# Tapuino_1_5.net
KiCad netlist of a schematic drawn in EAGLE
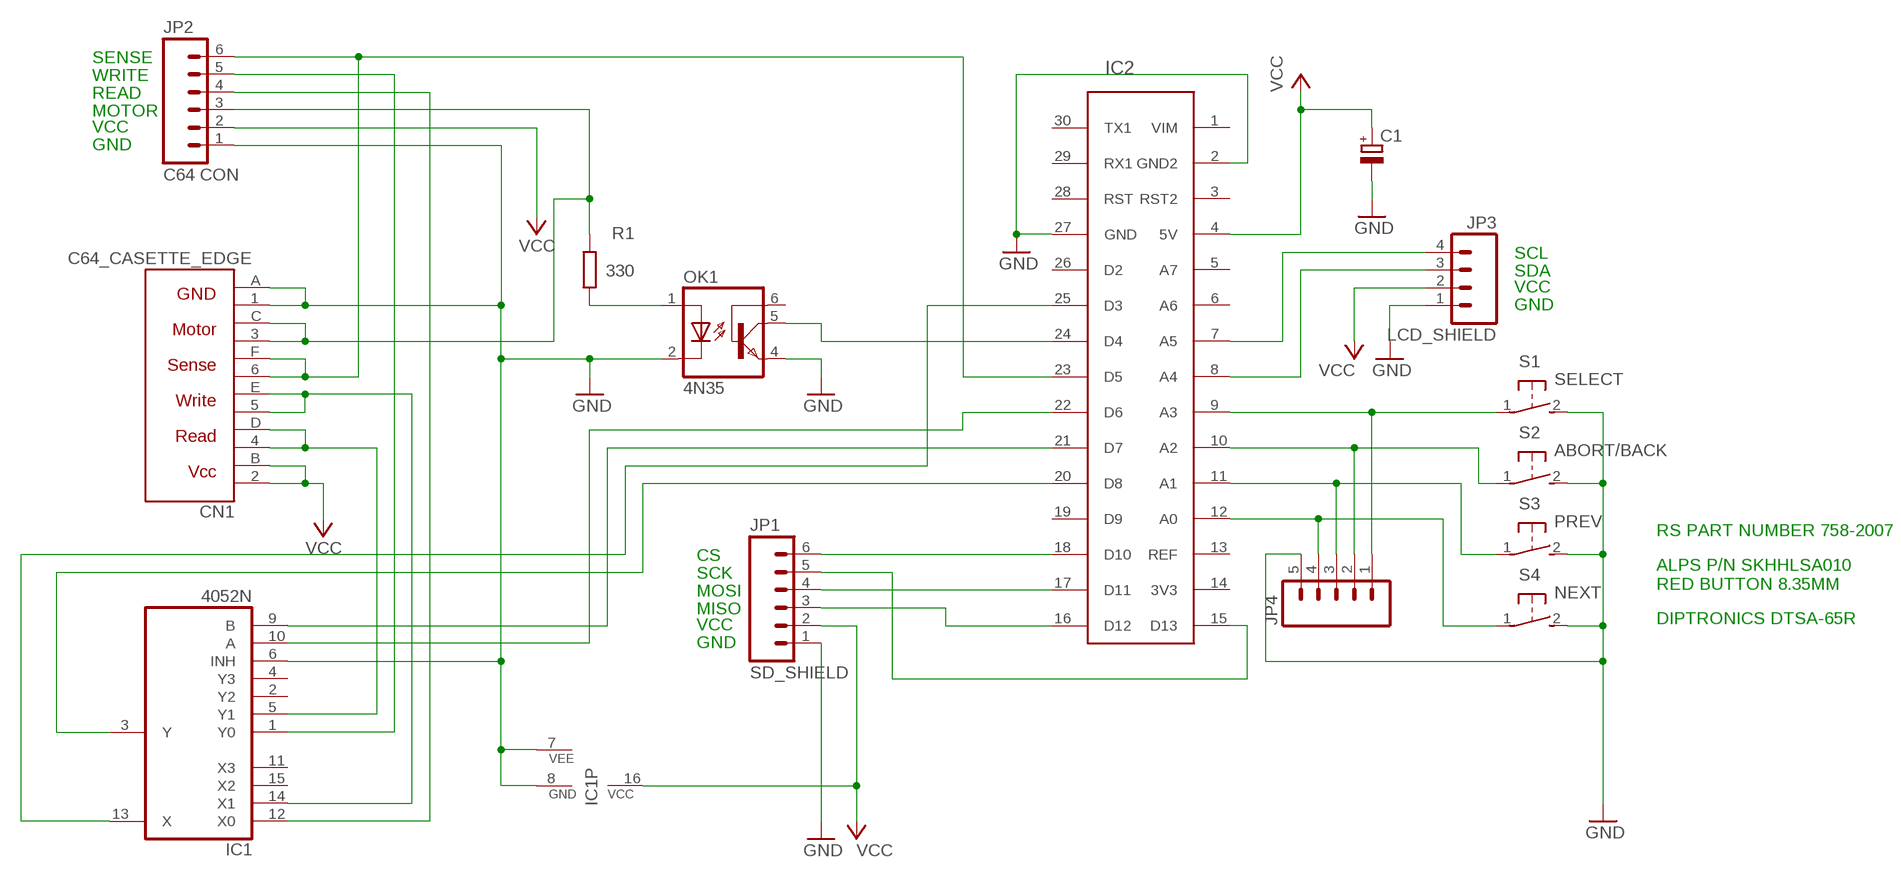
[diagram p0: schematic, sheet 1]

(export (version "E")
  (design (tool "Eeschema 10.0.6"))
  (components
    (comp (ref "C1")
      (value "CPOL-EUE2.5-6")
      (footprint "eagle-import:E2,5-6")
      (libsource (lib "eagle-import") (part "CPOL-EUE2.5-6"))
    )
    (comp (ref "CN1")
      (value "C64_CASETTE_EDGE")
      (footprint "eagle-import:C64_CASSETTE")
      (libsource (lib "eagle-import") (part "C64_CASETTE_EDGE"))
    )
    (comp (ref "IC1")
      (value "4052N")
      (footprint "eagle-import:DIL16")
      (libsource (lib "eagle-import") (part "4052N"))
    )
    (comp (ref "IC2")
      (value "ARDUINO_NANO_V3")
      (footprint "eagle-import:NANO_V3")
      (libsource (lib "eagle-import") (part "ARDUINO_NANO_V3"))
    )
    (comp (ref "JP1")
      (value "SD_SHIELD")
      (footprint "eagle-import:1X06_LOCK_LONGPADS")
      (libsource (lib "eagle-import") (part "M06LOCK_LONGPADS"))
    )
    (comp (ref "JP2")
      (value "C64 CON")
      (footprint "eagle-import:1X06_LOCK_LONGPADS")
      (libsource (lib "eagle-import") (part "M06LOCK_LONGPADS"))
    )
    (comp (ref "JP3")
      (value "LCD_SHIELD")
      (footprint "eagle-import:1X04_LOCK_LONGPADS")
      (libsource (lib "eagle-import") (part "M04LOCK_LONGPADS"))
    )
    (comp (ref "JP4")
      (value "M05LOCK_LONGPADS")
      (footprint "eagle-import:1X05_LOCK_LONGPADS")
      (libsource (lib "eagle-import") (part "M05LOCK_LONGPADS"))
    )
    (comp (ref "OK1")
      (value "4N35")
      (footprint "eagle-import:DIL06")
      (fields (field (name "MF") "FAIRCHILD SEMICONDUCTOR"))
      (libsource (lib "eagle-import") (part "4N35"))
    )
    (comp (ref "R1")
      (value "330")
      (footprint "eagle-import:0207_10")
      (libsource (lib "eagle-import") (part "R-EU_0207/10"))
    )
    (comp (ref "S1")
      (value "SELECT")
      (footprint "eagle-import:B3F-31XX")
      (fields (field (name "MPN") "B3F-3100"))
      (libsource (lib "eagle-import") (part "31-XX"))
    )
    (comp (ref "S2")
      (value "ABORT/BACK")
      (footprint "eagle-import:B3F-31XX")
      (fields (field (name "MPN") "B3F-3100"))
      (libsource (lib "eagle-import") (part "31-XX"))
    )
    (comp (ref "S3")
      (value "PREV")
      (footprint "eagle-import:B3F-31XX")
      (fields (field (name "MPN") "B3F-3100"))
      (libsource (lib "eagle-import") (part "31-XX"))
    )
    (comp (ref "S4")
      (value "NEXT")
      (footprint "eagle-import:B3F-31XX")
      (fields (field (name "MPN") "B3F-3100"))
      (libsource (lib "eagle-import") (part "31-XX"))
    )
  )
  (nets
    (net (code "1") (name "GND") (class "Default")
      (node (ref "C1") (pin "-") (pinfunction "-_-") (pintype "passive"))
      (node (ref "CN1") (pin "1") (pinfunction "GND1_1") (pintype "power_in"))
      (node (ref "CN1") (pin "A") (pinfunction "GND2_A") (pintype "power_in"))
      (node (ref "IC1") (pin "6") (pinfunction "INH_6") (pintype "input"))
      (node (ref "IC1") (pin "7") (pinfunction "VEE_7") (pintype "power_in"))
      (node (ref "IC1") (pin "8") (pinfunction "GND_8") (pintype "power_in"))
      (node (ref "IC2") (pin "2") (pinfunction "GND2_2") (pintype "bidirectional"))
      (node (ref "IC2") (pin "27") (pinfunction "GND_27") (pintype "bidirectional"))
      (node (ref "JP1") (pin "1") (pinfunction "1_1") (pintype "passive"))
      (node (ref "JP2") (pin "1") (pinfunction "1_1") (pintype "passive"))
      (node (ref "JP3") (pin "1") (pinfunction "1_1") (pintype "passive"))
      (node (ref "JP4") (pin "5") (pinfunction "5_5") (pintype "passive"))
      (node (ref "OK1") (pin "2") (pinfunction "C_2") (pintype "passive"))
      (node (ref "OK1") (pin "4") (pinfunction "EMI_4") (pintype "passive"))
      (node (ref "S1") (pin "2") (pinfunction "S_2") (pintype "passive"))
      (node (ref "S2") (pin "2") (pinfunction "S_2") (pintype "passive"))
      (node (ref "S3") (pin "2") (pinfunction "S_2") (pintype "passive"))
      (node (ref "S4") (pin "2") (pinfunction "S_2") (pintype "passive"))
    )
    (net (code "2") (name "Net-(CN1-MOTOR1)") (class "Default")
      (node (ref "CN1") (pin "3") (pinfunction "MOTOR1_3") (pintype "output"))
      (node (ref "CN1") (pin "C") (pinfunction "MOTOR2_C") (pintype "output"))
      (node (ref "JP2") (pin "3") (pinfunction "3_3") (pintype "passive"))
      (node (ref "R1") (pin "2") (pinfunction "2_2") (pintype "passive"))
    )
    (net (code "3") (name "Net-(CN1-READ1)") (class "Default")
      (node (ref "CN1") (pin "4") (pinfunction "READ1_4") (pintype "output"))
      (node (ref "CN1") (pin "D") (pinfunction "READ2_D") (pintype "output"))
      (node (ref "IC1") (pin "5") (pinfunction "Y1_5") (pintype "bidirectional"))
    )
    (net (code "4") (name "Net-(CN1-SENSE1)") (class "Default")
      (node (ref "CN1") (pin "6") (pinfunction "SENSE1_6") (pintype "input"))
      (node (ref "CN1") (pin "F") (pinfunction "SENSE2_F") (pintype "input"))
      (node (ref "IC2") (pin "23") (pinfunction "D5_23") (pintype "bidirectional"))
      (node (ref "JP2") (pin "6") (pinfunction "6_6") (pintype "passive"))
    )
    (net (code "5") (name "Net-(CN1-WRITE1)") (class "Default")
      (node (ref "CN1") (pin "5") (pinfunction "WRITE1_5") (pintype "input"))
      (node (ref "CN1") (pin "E") (pinfunction "WRITE2_E") (pintype "input"))
      (node (ref "IC1") (pin "14") (pinfunction "X1_14") (pintype "bidirectional"))
    )
    (net (code "6") (name "Net-(IC1A-A)") (class "Default")
      (node (ref "IC1") (pin "10") (pinfunction "A_10") (pintype "input"))
      (node (ref "IC2") (pin "22") (pinfunction "D6_22") (pintype "bidirectional"))
    )
    (net (code "7") (name "Net-(IC1A-B)") (class "Default")
      (node (ref "IC1") (pin "9") (pinfunction "B_9") (pintype "input"))
      (node (ref "IC2") (pin "21") (pinfunction "D7_21") (pintype "bidirectional"))
    )
    (net (code "8") (name "Net-(IC1A-X)") (class "Default")
      (node (ref "IC1") (pin "13") (pinfunction "X_13") (pintype "bidirectional"))
      (node (ref "IC2") (pin "25") (pinfunction "D3_25") (pintype "bidirectional"))
    )
    (net (code "9") (name "Net-(IC1A-X0)") (class "Default")
      (node (ref "IC1") (pin "12") (pinfunction "X0_12") (pintype "bidirectional"))
      (node (ref "JP2") (pin "4") (pinfunction "4_4") (pintype "passive"))
    )
    (net (code "10") (name "Net-(IC1A-Y)") (class "Default")
      (node (ref "IC1") (pin "3") (pinfunction "Y_3") (pintype "bidirectional"))
      (node (ref "IC2") (pin "20") (pinfunction "D8_20") (pintype "bidirectional"))
    )
    (net (code "11") (name "Net-(IC1A-Y0)") (class "Default")
      (node (ref "IC1") (pin "1") (pinfunction "Y0_1") (pintype "bidirectional"))
      (node (ref "JP2") (pin "5") (pinfunction "5_5") (pintype "passive"))
    )
    (net (code "12") (name "Net-(IC2-A0)") (class "Default")
      (node (ref "IC2") (pin "12") (pinfunction "A0_12") (pintype "bidirectional"))
      (node (ref "JP4") (pin "4") (pinfunction "4_4") (pintype "passive"))
      (node (ref "S4") (pin "1") (pinfunction "P_1") (pintype "passive"))
    )
    (net (code "13") (name "Net-(IC2-A1)") (class "Default")
      (node (ref "IC2") (pin "11") (pinfunction "A1_11") (pintype "bidirectional"))
      (node (ref "JP4") (pin "3") (pinfunction "3_3") (pintype "passive"))
      (node (ref "S3") (pin "1") (pinfunction "P_1") (pintype "passive"))
    )
    (net (code "14") (name "Net-(IC2-A2)") (class "Default")
      (node (ref "IC2") (pin "10") (pinfunction "A2_10") (pintype "bidirectional"))
      (node (ref "JP4") (pin "2") (pinfunction "2_2") (pintype "passive"))
      (node (ref "S2") (pin "1") (pinfunction "P_1") (pintype "passive"))
    )
    (net (code "15") (name "Net-(IC2-A3)") (class "Default")
      (node (ref "IC2") (pin "9") (pinfunction "A3_9") (pintype "bidirectional"))
      (node (ref "JP4") (pin "1") (pinfunction "1_1") (pintype "passive"))
      (node (ref "S1") (pin "1") (pinfunction "P_1") (pintype "passive"))
    )
    (net (code "16") (name "Net-(IC2-A4)") (class "Default")
      (node (ref "IC2") (pin "8") (pinfunction "A4_8") (pintype "bidirectional"))
      (node (ref "JP3") (pin "3") (pinfunction "3_3") (pintype "passive"))
    )
    (net (code "17") (name "Net-(IC2-A5)") (class "Default")
      (node (ref "IC2") (pin "7") (pinfunction "A5_7") (pintype "bidirectional"))
      (node (ref "JP3") (pin "4") (pinfunction "4_4") (pintype "passive"))
    )
    (net (code "18") (name "Net-(IC2-D4)") (class "Default")
      (node (ref "IC2") (pin "24") (pinfunction "D4_24") (pintype "bidirectional"))
      (node (ref "OK1") (pin "5") (pinfunction "COL_5") (pintype "passive"))
    )
    (net (code "19") (name "Net-(IC2-D10)") (class "Default")
      (node (ref "IC2") (pin "18") (pinfunction "D10_18") (pintype "bidirectional"))
      (node (ref "JP1") (pin "6") (pinfunction "6_6") (pintype "passive"))
    )
    (net (code "20") (name "Net-(IC2-D11)") (class "Default")
      (node (ref "IC2") (pin "17") (pinfunction "D11_17") (pintype "bidirectional"))
      (node (ref "JP1") (pin "4") (pinfunction "4_4") (pintype "passive"))
    )
    (net (code "21") (name "Net-(IC2-D12)") (class "Default")
      (node (ref "IC2") (pin "16") (pinfunction "D12_16") (pintype "bidirectional"))
      (node (ref "JP1") (pin "3") (pinfunction "3_3") (pintype "passive"))
    )
    (net (code "22") (name "Net-(IC2-D13)") (class "Default")
      (node (ref "IC2") (pin "15") (pinfunction "D13_15") (pintype "bidirectional"))
      (node (ref "JP1") (pin "5") (pinfunction "5_5") (pintype "passive"))
    )
    (net (code "23") (name "Net-(OK1-A)") (class "Default")
      (node (ref "OK1") (pin "1") (pinfunction "A_1") (pintype "passive"))
      (node (ref "R1") (pin "1") (pinfunction "1_1") (pintype "passive"))
    )
    (net (code "24") (name "VCC") (class "Default")
      (node (ref "C1") (pin "+") (pinfunction "+_+") (pintype "passive"))
      (node (ref "CN1") (pin "2") (pinfunction "VCC1_2") (pintype "power_in"))
      (node (ref "CN1") (pin "B") (pinfunction "VCC2_B") (pintype "power_in"))
      (node (ref "IC1") (pin "16") (pinfunction "VCC_16") (pintype "power_in"))
      (node (ref "IC2") (pin "4") (pinfunction "5V_4") (pintype "bidirectional"))
      (node (ref "JP1") (pin "2") (pinfunction "2_2") (pintype "passive"))
      (node (ref "JP2") (pin "2") (pinfunction "2_2") (pintype "passive"))
      (node (ref "JP3") (pin "2") (pinfunction "2_2") (pintype "passive"))
    )
    (net (code "25") (name "unconnected-(IC1A-X2-Pad15)") (class "Default")
      (node (ref "IC1") (pin "15") (pinfunction "X2_15") (pintype "bidirectional"))
    )
    (net (code "26") (name "unconnected-(IC1A-X3-Pad11)") (class "Default")
      (node (ref "IC1") (pin "11") (pinfunction "X3_11") (pintype "bidirectional"))
    )
    (net (code "27") (name "unconnected-(IC1A-Y2-Pad2)") (class "Default")
      (node (ref "IC1") (pin "2") (pinfunction "Y2_2") (pintype "bidirectional"))
    )
    (net (code "28") (name "unconnected-(IC1A-Y3-Pad4)") (class "Default")
      (node (ref "IC1") (pin "4") (pinfunction "Y3_4") (pintype "bidirectional"))
    )
    (net (code "29") (name "unconnected-(IC2-3V3-Pad14)") (class "Default")
      (node (ref "IC2") (pin "14") (pinfunction "3V3_14") (pintype "bidirectional"))
    )
    (net (code "30") (name "unconnected-(IC2-A6-Pad6)") (class "Default")
      (node (ref "IC2") (pin "6") (pinfunction "A6_6") (pintype "bidirectional"))
    )
    (net (code "31") (name "unconnected-(IC2-A7-Pad5)") (class "Default")
      (node (ref "IC2") (pin "5") (pinfunction "A7_5") (pintype "bidirectional"))
    )
    (net (code "32") (name "unconnected-(IC2-D2-Pad26)") (class "Default")
      (node (ref "IC2") (pin "26") (pinfunction "D2_26") (pintype "bidirectional"))
    )
    (net (code "33") (name "unconnected-(IC2-D9-Pad19)") (class "Default")
      (node (ref "IC2") (pin "19") (pinfunction "D9_19") (pintype "bidirectional"))
    )
    (net (code "34") (name "unconnected-(IC2-REF-Pad13)") (class "Default")
      (node (ref "IC2") (pin "13") (pinfunction "REF_13") (pintype "bidirectional"))
    )
    (net (code "35") (name "unconnected-(IC2-RST-Pad28)") (class "Default")
      (node (ref "IC2") (pin "28") (pinfunction "RST_28") (pintype "bidirectional"))
    )
    (net (code "36") (name "unconnected-(IC2-RST2-Pad3)") (class "Default")
      (node (ref "IC2") (pin "3") (pinfunction "RST2_3") (pintype "bidirectional"))
    )
    (net (code "37") (name "unconnected-(IC2-RX1-Pad29)") (class "Default")
      (node (ref "IC2") (pin "29") (pinfunction "RX1_29") (pintype "bidirectional"))
    )
    (net (code "38") (name "unconnected-(IC2-TX1-Pad30)") (class "Default")
      (node (ref "IC2") (pin "30") (pinfunction "TX1_30") (pintype "bidirectional"))
    )
    (net (code "39") (name "unconnected-(IC2-VIM-Pad1)") (class "Default")
      (node (ref "IC2") (pin "1") (pinfunction "VIM_1") (pintype "bidirectional"))
    )
    (net (code "40") (name "unconnected-(OK1-BAS-Pad6)") (class "Default")
      (node (ref "OK1") (pin "6") (pinfunction "BAS_6") (pintype "passive"))
    )
  )
)
